# E3-Thermal-Sensor_v1.net
KiCad netlist of a schematic drawn in EAGLE
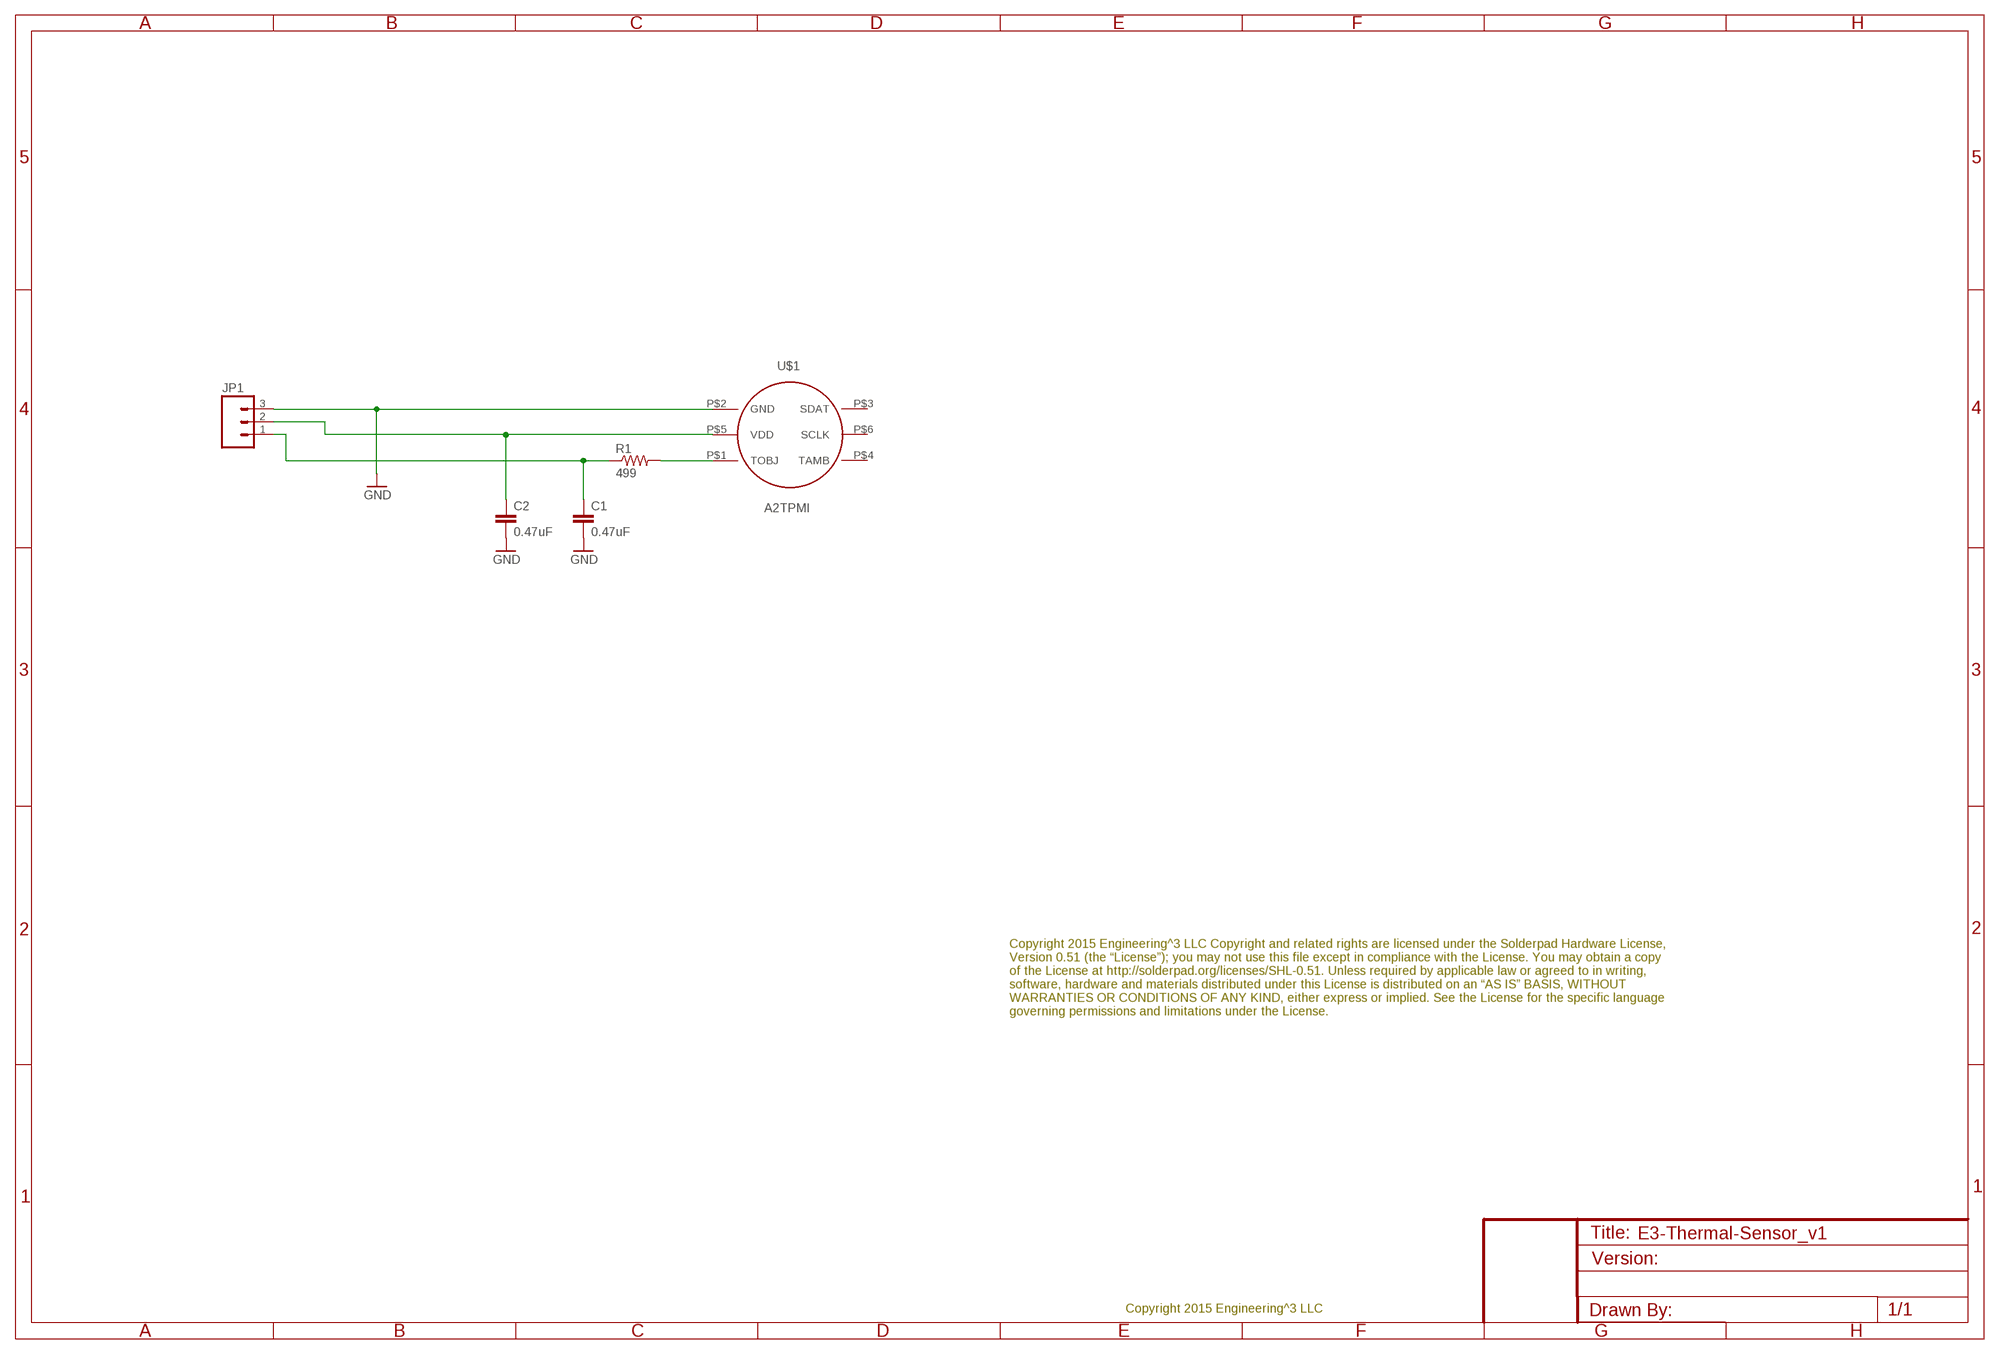
[diagram p0: schematic, sheet 1]

(export (version "E")
  (design (tool "Eeschema 10.0.6"))
  (components
    (comp (ref "C1")
      (value "0.47uF")
      (footprint "eagle-import:C0402")
      (libsource (lib "eagle-import") (part "CAP0402"))
    )
    (comp (ref "C2")
      (value "0.47uF")
      (footprint "eagle-import:C0402")
      (libsource (lib "eagle-import") (part "CAP0402"))
    )
    (comp (ref "JP1")
      (value "M03PTH")
      (footprint "eagle-import:1X03")
      (libsource (lib "eagle-import") (part "M03PTH"))
    )
    (comp (ref "R1")
      (value "499")
      (footprint "eagle-import:C0402")
      (libsource (lib "eagle-import") (part "RESISTOR0402"))
    )
    (comp (ref "U$1")
      (value "A2TPMI")
      (footprint "eagle-import:A2TPMI")
      (libsource (lib "eagle-import") (part "A2TPMI"))
    )
  )
  (nets
    (net (code "1") (name "GND") (class "Default")
      (node (ref "C1") (pin "2") (pinfunction "2_2") (pintype "passive"))
      (node (ref "C2") (pin "2") (pinfunction "2_2") (pintype "passive"))
      (node (ref "JP1") (pin "3") (pinfunction "3_3") (pintype "passive"))
      (node (ref "U$1") (pin "P$2") (pinfunction "GND_P$2") (pintype "power_in"))
    )
    (net (code "2") (name "Net-(C1-Pad1)") (class "Default")
      (node (ref "C1") (pin "1") (pinfunction "1_1") (pintype "passive"))
      (node (ref "JP1") (pin "1") (pinfunction "1_1") (pintype "passive"))
      (node (ref "R1") (pin "1") (pinfunction "1_1") (pintype "passive"))
    )
    (net (code "3") (name "Net-(U$1-TOBJ)") (class "Default")
      (node (ref "R1") (pin "2") (pinfunction "2_2") (pintype "passive"))
      (node (ref "U$1") (pin "P$1") (pinfunction "TOBJ_P$1") (pintype "output"))
    )
    (net (code "4") (name "Net-(U$1-VDD)") (class "Default")
      (node (ref "C2") (pin "1") (pinfunction "1_1") (pintype "passive"))
      (node (ref "JP1") (pin "2") (pinfunction "2_2") (pintype "passive"))
      (node (ref "U$1") (pin "P$5") (pinfunction "VDD_P$5") (pintype "power_in"))
    )
    (net (code "5") (name "unconnected-(U$1-SCLK-PadP$6)") (class "Default")
      (node (ref "U$1") (pin "P$6") (pinfunction "SCLK_P$6") (pintype "bidirectional"))
    )
    (net (code "6") (name "unconnected-(U$1-SDAT-PadP$3)") (class "Default")
      (node (ref "U$1") (pin "P$3") (pinfunction "SDAT_P$3") (pintype "bidirectional"))
    )
    (net (code "7") (name "unconnected-(U$1-TAMB-PadP$4)") (class "Default")
      (node (ref "U$1") (pin "P$4") (pinfunction "TAMB_P$4") (pintype "bidirectional"))
    )
  )
)
